# Sheet4.net
KiCad netlist of a schematic drawn in Altium Designer
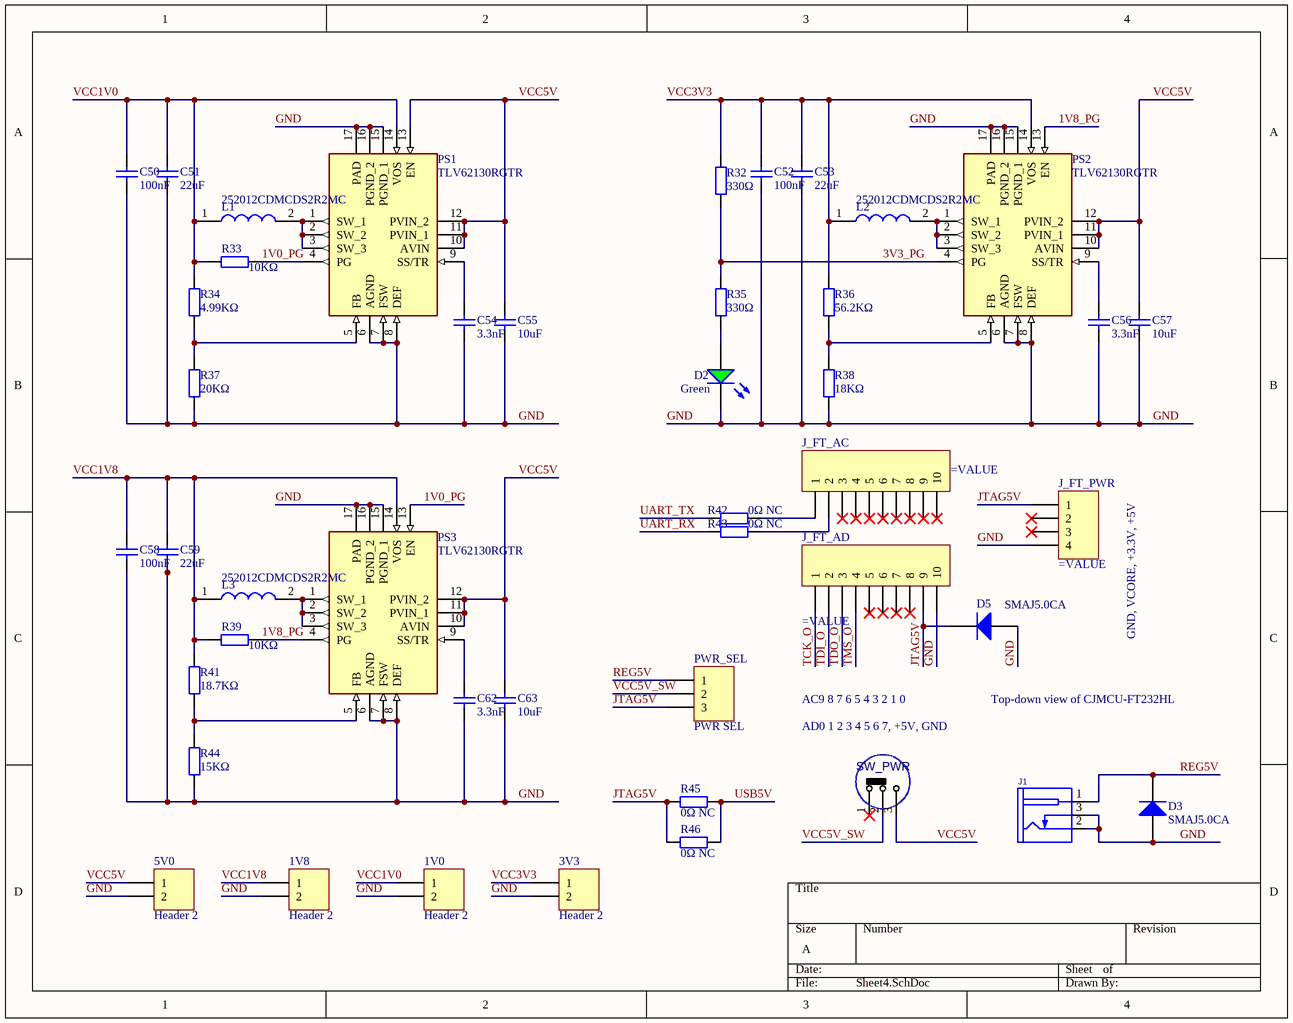
[diagram p0: Sheet4.SchDoc]

(export (version "E")
  (design (tool "Eeschema 10.0.6"))
  (components
    (comp (ref "1V0")
      (value "Header 2")
      (footprint "HDR1X2")
      (description "Header, 2-Pin")
      (fields (field (name "PUBLISHER") "Altium Limited"))
      (libsource (lib "Miscellaneous Connectors") (part "Header 2"))
    )
    (comp (ref "1V8")
      (value "Header 2")
      (footprint "HDR1X2")
      (description "Header, 2-Pin")
      (fields (field (name "PUBLISHER") "Altium Limited"))
      (libsource (lib "Miscellaneous Connectors") (part "Header 2"))
    )
    (comp (ref "3V3")
      (value "Header 2")
      (footprint "HDR1X2")
      (description "Header, 2-Pin")
      (fields (field (name "PUBLISHER") "Altium Limited"))
      (libsource (lib "Miscellaneous Connectors") (part "Header 2"))
    )
    (comp (ref "5V0")
      (value "Header 2")
      (footprint "HDR1X2")
      (description "Header, 2-Pin")
      (fields (field (name "PUBLISHER") "Altium Limited"))
      (libsource (lib "Miscellaneous Connectors") (part "Header 2"))
    )
    (comp (ref "C50")
      (value "100nF")
      (footprint "1206_C")
      (description "贴片电容")
      (libsource (lib "Cap") (part "1206 100nF (104) 10% 50V"))
    )
    (comp (ref "C51")
      (value "22uF")
      (footprint "0805_C")
      (description "贴片电容")
      (libsource (lib "Cap") (part "0805 22uF (226) 20% 25V"))
    )
    (comp (ref "C52")
      (value "100nF")
      (footprint "1206_C")
      (description "贴片电容")
      (libsource (lib "Cap") (part "1206 100nF (104) 10% 50V"))
    )
    (comp (ref "C53")
      (value "22uF")
      (footprint "0805_C")
      (description "贴片电容")
      (libsource (lib "Cap") (part "0805 22uF (226) 20% 25V"))
    )
    (comp (ref "C54")
      (value "3.3nF")
      (footprint "0805_C")
      (description "贴片电容")
      (libsource (lib "Cap") (part "0805 3.3nF (332) 10% 50V"))
    )
    (comp (ref "C55")
      (value "10uF")
      (footprint "1206_C")
      (description "贴片电容")
      (libsource (lib "Cap") (part "1206 10uF (106) 10% 50V"))
    )
    (comp (ref "C56")
      (value "3.3nF")
      (footprint "0805_C")
      (description "贴片电容")
      (libsource (lib "Cap") (part "0805 3.3nF (332) 10% 50V"))
    )
    (comp (ref "C57")
      (value "10uF")
      (footprint "1206_C")
      (description "贴片电容")
      (libsource (lib "Cap") (part "1206 10uF (106) 10% 50V"))
    )
    (comp (ref "C58")
      (value "100nF")
      (footprint "1206_C")
      (description "贴片电容")
      (libsource (lib "Cap") (part "1206 100nF (104) 10% 50V"))
    )
    (comp (ref "C59")
      (value "22uF")
      (footprint "0805_C")
      (description "贴片电容")
      (libsource (lib "Cap") (part "0805 22uF (226) 20% 25V"))
    )
    (comp (ref "C62")
      (value "3.3nF")
      (footprint "0805_C")
      (description "贴片电容")
      (libsource (lib "Cap") (part "0805 3.3nF (332) 10% 50V"))
    )
    (comp (ref "C63")
      (value "10uF")
      (footprint "1206_C")
      (description "贴片电容")
      (libsource (lib "Cap") (part "1206 10uF (106) 10% 50V"))
    )
    (comp (ref "D2")
      (value "Green")
      (footprint "0805_LED_S1")
      (description "发光二极管")
      (libsource (lib "LED") (part "0805 翠绿"))
    )
    (comp (ref "D3")
      (value "SMAJ5.0CA")
      (footprint "SMA(DO-214AC)_S1")
      (description "二极管 TVS")
      (libsource (lib "Diode") (part "SMA(DO-214AC) SS210"))
    )
    (comp (ref "D5")
      (value "SMAJ5.0CA")
      (footprint "SMA(DO-214AC)_S1")
      (description "二极管 TVS")
      (libsource (lib "Diode") (part "SMA(DO-214AC) SS210"))
    )
    (comp (ref "J1")
      (value "DC_POWER_JACK")
      (footprint "JAC_PWR2MM")
      (description "CONN, PWR JACK DC, PLUG DIAM 2.0MM RA THD")
      (fields
        (field (name "MANF") "CUI STACK")
        (field (name "MANF_P#") "PJ-202A, PJ-002AH, PJ-102AH, KLDX-0202")
      )
      (libsource (lib "Connector Power") (part "CONN_PWR_JACK2MM"))
    )
    (comp (ref "J_FT_AC")
      (value "~")
      (footprint "HDR1X10")
      (description "Header, 10-Pin")
      (fields (field (name "PUBLISHER") "Altium Limited"))
      (libsource (lib "Miscellaneous Connectors") (part "Header 10"))
    )
    (comp (ref "J_FT_AD")
      (value "~")
      (footprint "HDR1X10")
      (description "Header, 10-Pin")
      (fields (field (name "PUBLISHER") "Altium Limited"))
      (libsource (lib "Miscellaneous Connectors") (part "Header 10"))
    )
    (comp (ref "J_FT_PWR")
      (value "~")
      (footprint "HDR1X4")
      (description "Header, 4-Pin")
      (fields (field (name "PUBLISHER") "Altium Limited"))
      (libsource (lib "Miscellaneous Connectors") (part "Header 4"))
    )
    (comp (ref "L1")
      (value "252012CDMCDS2R2MC")
      (footprint "SamacSys:INDPM2520X120N")
      (description "Inductor")
      (fields (field (name "MANUFACTURER_PART_NUMBER") "252012CDMCDS‐2R2MC"))
      (libsource (lib "*") (part "252012CDMCDS2R2MC"))
    )
    (comp (ref "L2")
      (value "252012CDMCDS2R2MC")
      (footprint "SamacSys:INDPM2520X120N")
      (description "Inductor")
      (fields (field (name "MANUFACTURER_PART_NUMBER") "252012CDMCDS‐2R2MC"))
      (libsource (lib "*") (part "252012CDMCDS2R2MC"))
    )
    (comp (ref "L3")
      (value "252012CDMCDS2R2MC")
      (footprint "SamacSys:INDPM2520X120N")
      (description "Inductor")
      (fields (field (name "MANUFACTURER_PART_NUMBER") "252012CDMCDS‐2R2MC"))
      (libsource (lib "*") (part "252012CDMCDS2R2MC"))
    )
    (comp (ref "PS1")
      (value "TLV62130RGTR")
      (footprint "SamacSys:QFN50P300X300X100-17N-D")
      (description "Power Supply")
      (fields (field (name "MOUSER PART NUMBER") "595-TLV62130RGTR"))
      (libsource (lib "*") (part "TLV62130RGTR"))
    )
    (comp (ref "PS2")
      (value "TLV62130RGTR")
      (footprint "SamacSys:QFN50P300X300X100-17N-D")
      (description "Power Supply")
      (fields (field (name "MOUSER PART NUMBER") "595-TLV62130RGTR"))
      (libsource (lib "*") (part "TLV62130RGTR"))
    )
    (comp (ref "PS3")
      (value "TLV62130RGTR")
      (footprint "SamacSys:QFN50P300X300X100-17N-D")
      (description "Power Supply")
      (fields (field (name "MOUSER PART NUMBER") "595-TLV62130RGTR"))
      (libsource (lib "*") (part "TLV62130RGTR"))
    )
    (comp (ref "PWR_SEL")
      (value "PWR SEL")
      (footprint "HDR1X3")
      (description "Header, 3-Pin")
      (fields (field (name "PUBLISHER") "Altium Limited"))
      (libsource (lib "Miscellaneous Connectors") (part "Header 3"))
    )
    (comp (ref "R32")
      (value "330Ω")
      (footprint "0805_R")
      (description "贴片电阻")
      (libsource (lib "RES") (part "0805 330Ω (3300) 1%"))
    )
    (comp (ref "R33")
      (value "10KΩ")
      (footprint "1206_R")
      (description "贴片电阻")
      (libsource (lib "RES") (part "1206 10KΩ (1002) 1%"))
    )
    (comp (ref "R34")
      (value "4.99KΩ")
      (footprint "0805_R")
      (description "贴片电阻")
      (libsource (lib "RES") (part "0805 4.99KΩ (4991) 1%"))
    )
    (comp (ref "R35")
      (value "330Ω")
      (footprint "0805_R")
      (description "贴片电阻")
      (libsource (lib "RES") (part "0805 330Ω (3300) 1%"))
    )
    (comp (ref "R36")
      (value "56.2KΩ")
      (footprint "0805_R")
      (description "贴片电阻 56.2k")
      (libsource (lib "RES") (part "0805 56KΩ (5602) 1%"))
    )
    (comp (ref "R37")
      (value "20KΩ")
      (footprint "0805_R")
      (description "贴片电阻")
      (libsource (lib "RES") (part "0805 20KΩ (2002) 1%"))
    )
    (comp (ref "R38")
      (value "18KΩ")
      (footprint "0805_R")
      (description "贴片电阻")
      (libsource (lib "RES") (part "0805 18KΩ (1802) 1%"))
    )
    (comp (ref "R39")
      (value "10KΩ")
      (footprint "1206_R")
      (description "贴片电阻")
      (libsource (lib "RES") (part "1206 10KΩ (1002) 1%"))
    )
    (comp (ref "R41")
      (value "18.7KΩ")
      (footprint "0805_R")
      (description "贴片电阻 18.7k")
      (libsource (lib "RES") (part "0805 18KΩ (1802) 1%"))
    )
    (comp (ref "R42")
      (value "0Ω NC")
      (footprint "0805_R")
      (description "贴片电阻")
      (libsource (lib "RES") (part "0805 0Ω (0R0) 1%"))
    )
    (comp (ref "R43")
      (value "0Ω NC")
      (footprint "0805_R")
      (description "贴片电阻")
      (libsource (lib "RES") (part "0805 0Ω (0R0) 1%"))
    )
    (comp (ref "R44")
      (value "15KΩ")
      (footprint "0805_R")
      (description "贴片电阻")
      (libsource (lib "RES") (part "0805 15KΩ (1502) 1%"))
    )
    (comp (ref "R45")
      (value "0Ω NC")
      (footprint "0805_R")
      (description "贴片电阻")
      (libsource (lib "RES") (part "0805 0Ω (0R0) 1%"))
    )
    (comp (ref "R46")
      (value "0Ω NC")
      (footprint "0805_R")
      (description "贴片电阻")
      (libsource (lib "RES") (part "0805 0Ω (0R0) 1%"))
    )
    (comp (ref "SW_PWR")
      (value "SlideSwitch")
      (footprint "SWSLIDT_SPDT_S_8X4")
      (description "SWITCH, SLIDE, SPDT, 8.6X4.3mm, THD")
      (fields (field (name "MANF") "C&K") (field (name "MANF_PART#") "OS102011MS2QN1"))
      (libsource (lib "Switch Slide") (part "SWSLIDT_SPDT_S_8X4"))
    )
  )
  (nets
    (net (code "1") (name "/1V0_PG") (class "Default")
      (node (ref "PS1") (pin "4") (pinfunction "PG_4") (pintype "output"))
      (node (ref "PS3") (pin "13") (pinfunction "EN_13") (pintype "input"))
      (node (ref "R33") (pin "2") (pinfunction "2_2") (pintype "passive"))
    )
    (net (code "2") (name "/1V8_PG") (class "Default")
      (node (ref "PS2") (pin "13") (pinfunction "EN_13") (pintype "input"))
      (node (ref "PS3") (pin "4") (pinfunction "PG_4") (pintype "output"))
      (node (ref "R39") (pin "2") (pinfunction "2_2") (pintype "passive"))
    )
    (net (code "3") (name "/3V3_PG") (class "Default")
      (node (ref "PS2") (pin "4") (pinfunction "PG_4") (pintype "output"))
      (node (ref "R32") (pin "1") (pinfunction "1_1") (pintype "passive"))
      (node (ref "R35") (pin "2") (pinfunction "2_2") (pintype "passive"))
    )
    (net (code "4") (name "/GND") (class "Default")
      (node (ref "1V0") (pin "2") (pinfunction "2_2") (pintype "passive"))
      (node (ref "1V8") (pin "2") (pinfunction "2_2") (pintype "passive"))
      (node (ref "3V3") (pin "2") (pinfunction "2_2") (pintype "passive"))
      (node (ref "5V0") (pin "2") (pinfunction "2_2") (pintype "passive"))
      (node (ref "C50") (pin "1") (pinfunction "1_1") (pintype "passive"))
      (node (ref "C51") (pin "1") (pinfunction "1_1") (pintype "passive"))
      (node (ref "C52") (pin "1") (pinfunction "1_1") (pintype "passive"))
      (node (ref "C53") (pin "1") (pinfunction "1_1") (pintype "passive"))
      (node (ref "C54") (pin "1") (pinfunction "1_1") (pintype "passive"))
      (node (ref "C55") (pin "1") (pinfunction "1_1") (pintype "passive"))
      (node (ref "C56") (pin "1") (pinfunction "1_1") (pintype "passive"))
      (node (ref "C57") (pin "1") (pinfunction "1_1") (pintype "passive"))
      (node (ref "C58") (pin "1") (pinfunction "1_1") (pintype "passive"))
      (node (ref "C59") (pin "1") (pinfunction "1_1") (pintype "passive"))
      (node (ref "C62") (pin "1") (pinfunction "1_1") (pintype "passive"))
      (node (ref "C63") (pin "1") (pinfunction "1_1") (pintype "passive"))
      (node (ref "D2") (pin "K") (pinfunction "K_K") (pintype "passive"))
      (node (ref "D3") (pin "1") (pinfunction "A_1") (pintype "passive"))
      (node (ref "D5") (pin "1") (pinfunction "A_1") (pintype "passive"))
      (node (ref "J1") (pin "2") (pinfunction "SLEEVE_2") (pintype "power_in"))
      (node (ref "J1") (pin "3") (pinfunction "INSERTION_DET_3") (pintype "power_in"))
      (node (ref "J_FT_AD") (pin "10") (pinfunction "10_10") (pintype "passive"))
      (node (ref "J_FT_PWR") (pin "4") (pinfunction "4_4") (pintype "passive"))
      (node (ref "PS1") (pin "15") (pinfunction "PGND_1_15") (pintype "power_in"))
      (node (ref "PS1") (pin "16") (pinfunction "PGND_2_16") (pintype "power_in"))
      (node (ref "PS1") (pin "17") (pinfunction "PAD_17") (pintype "power_in"))
      (node (ref "PS1") (pin "6") (pinfunction "AGND_6") (pintype "power_in"))
      (node (ref "PS1") (pin "7") (pinfunction "FSW_7") (pintype "input"))
      (node (ref "PS1") (pin "8") (pinfunction "DEF_8") (pintype "input"))
      (node (ref "PS2") (pin "15") (pinfunction "PGND_1_15") (pintype "power_in"))
      (node (ref "PS2") (pin "16") (pinfunction "PGND_2_16") (pintype "power_in"))
      (node (ref "PS2") (pin "17") (pinfunction "PAD_17") (pintype "power_in"))
      (node (ref "PS2") (pin "6") (pinfunction "AGND_6") (pintype "power_in"))
      (node (ref "PS2") (pin "7") (pinfunction "FSW_7") (pintype "input"))
      (node (ref "PS2") (pin "8") (pinfunction "DEF_8") (pintype "input"))
      (node (ref "PS3") (pin "15") (pinfunction "PGND_1_15") (pintype "power_in"))
      (node (ref "PS3") (pin "16") (pinfunction "PGND_2_16") (pintype "power_in"))
      (node (ref "PS3") (pin "17") (pinfunction "PAD_17") (pintype "power_in"))
      (node (ref "PS3") (pin "6") (pinfunction "AGND_6") (pintype "power_in"))
      (node (ref "PS3") (pin "7") (pinfunction "FSW_7") (pintype "input"))
      (node (ref "PS3") (pin "8") (pinfunction "DEF_8") (pintype "input"))
      (node (ref "R37") (pin "1") (pinfunction "1_1") (pintype "passive"))
      (node (ref "R38") (pin "1") (pinfunction "1_1") (pintype "passive"))
      (node (ref "R44") (pin "1") (pinfunction "1_1") (pintype "passive"))
    )
    (net (code "5") (name "/JTAG5V") (class "Default")
      (node (ref "D5") (pin "2") (pinfunction "K_2") (pintype "passive"))
      (node (ref "J_FT_AD") (pin "9") (pinfunction "9_9") (pintype "passive"))
      (node (ref "J_FT_PWR") (pin "1") (pinfunction "1_1") (pintype "passive"))
      (node (ref "PWR_SEL") (pin "3") (pinfunction "3_3") (pintype "passive"))
      (node (ref "R45") (pin "1") (pinfunction "1_1") (pintype "passive"))
      (node (ref "R46") (pin "1") (pinfunction "1_1") (pintype "passive"))
    )
    (net (code "6") (name "/REG5V") (class "Default")
      (node (ref "D3") (pin "2") (pinfunction "K_2") (pintype "passive"))
      (node (ref "J1") (pin "1") (pinfunction "TIP_1") (pintype "power_in"))
      (node (ref "PWR_SEL") (pin "1") (pinfunction "1_1") (pintype "passive"))
    )
    (net (code "7") (name "/TCK_O") (class "Default")
      (node (ref "J_FT_AD") (pin "1") (pinfunction "1_1") (pintype "passive"))
    )
    (net (code "8") (name "/TDI_O") (class "Default")
      (node (ref "J_FT_AD") (pin "2") (pinfunction "2_2") (pintype "passive"))
    )
    (net (code "9") (name "/TDO_O") (class "Default")
      (node (ref "J_FT_AD") (pin "3") (pinfunction "3_3") (pintype "passive"))
    )
    (net (code "10") (name "/TMS_O") (class "Default")
      (node (ref "J_FT_AD") (pin "4") (pinfunction "4_4") (pintype "passive"))
    )
    (net (code "11") (name "/UART_RX") (class "Default")
      (node (ref "R43") (pin "1") (pinfunction "1_1") (pintype "passive"))
    )
    (net (code "12") (name "/UART_TX") (class "Default")
      (node (ref "R42") (pin "1") (pinfunction "1_1") (pintype "passive"))
    )
    (net (code "13") (name "/USB5V") (class "Default")
      (node (ref "R45") (pin "2") (pinfunction "2_2") (pintype "passive"))
      (node (ref "R46") (pin "2") (pinfunction "2_2") (pintype "passive"))
    )
    (net (code "14") (name "/VCC1V0") (class "Default")
      (node (ref "1V0") (pin "1") (pinfunction "1_1") (pintype "passive"))
      (node (ref "C50") (pin "2") (pinfunction "2_2") (pintype "passive"))
      (node (ref "C51") (pin "2") (pinfunction "2_2") (pintype "passive"))
      (node (ref "L1") (pin "1") (pinfunction "1_1") (pintype "passive"))
      (node (ref "PS1") (pin "14") (pinfunction "VOS_14") (pintype "input"))
      (node (ref "R33") (pin "1") (pinfunction "1_1") (pintype "passive"))
      (node (ref "R34") (pin "2") (pinfunction "2_2") (pintype "passive"))
    )
    (net (code "15") (name "/VCC1V8") (class "Default")
      (node (ref "1V8") (pin "1") (pinfunction "1_1") (pintype "passive"))
      (node (ref "C58") (pin "2") (pinfunction "2_2") (pintype "passive"))
      (node (ref "C59") (pin "2") (pinfunction "2_2") (pintype "passive"))
      (node (ref "L3") (pin "1") (pinfunction "1_1") (pintype "passive"))
      (node (ref "PS3") (pin "14") (pinfunction "VOS_14") (pintype "input"))
      (node (ref "R39") (pin "1") (pinfunction "1_1") (pintype "passive"))
      (node (ref "R41") (pin "2") (pinfunction "2_2") (pintype "passive"))
    )
    (net (code "16") (name "/VCC3V3") (class "Default")
      (node (ref "3V3") (pin "1") (pinfunction "1_1") (pintype "passive"))
      (node (ref "C52") (pin "2") (pinfunction "2_2") (pintype "passive"))
      (node (ref "C53") (pin "2") (pinfunction "2_2") (pintype "passive"))
      (node (ref "L2") (pin "1") (pinfunction "1_1") (pintype "passive"))
      (node (ref "PS2") (pin "14") (pinfunction "VOS_14") (pintype "input"))
      (node (ref "R32") (pin "2") (pinfunction "2_2") (pintype "passive"))
      (node (ref "R36") (pin "2") (pinfunction "2_2") (pintype "passive"))
    )
    (net (code "17") (name "/VCC5V") (class "Default")
      (node (ref "5V0") (pin "1") (pinfunction "1_1") (pintype "passive"))
      (node (ref "C55") (pin "2") (pinfunction "2_2") (pintype "passive"))
      (node (ref "C57") (pin "2") (pinfunction "2_2") (pintype "passive"))
      (node (ref "C63") (pin "2") (pinfunction "2_2") (pintype "passive"))
      (node (ref "PS1") (pin "10") (pinfunction "AVIN_10") (pintype "power_in"))
      (node (ref "PS1") (pin "11") (pinfunction "PVIN_1_11") (pintype "power_in"))
      (node (ref "PS1") (pin "12") (pinfunction "PVIN_2_12") (pintype "power_in"))
      (node (ref "PS1") (pin "13") (pinfunction "EN_13") (pintype "input"))
      (node (ref "PS2") (pin "10") (pinfunction "AVIN_10") (pintype "power_in"))
      (node (ref "PS2") (pin "11") (pinfunction "PVIN_1_11") (pintype "power_in"))
      (node (ref "PS2") (pin "12") (pinfunction "PVIN_2_12") (pintype "power_in"))
      (node (ref "PS3") (pin "10") (pinfunction "AVIN_10") (pintype "power_in"))
      (node (ref "PS3") (pin "11") (pinfunction "PVIN_1_11") (pintype "power_in"))
      (node (ref "PS3") (pin "12") (pinfunction "PVIN_2_12") (pintype "power_in"))
      (node (ref "SW_PWR") (pin "3") (pinfunction "P4_3") (pintype "passive"))
    )
    (net (code "18") (name "/VCC5V_SW") (class "Default")
      (node (ref "PWR_SEL") (pin "2") (pinfunction "2_2") (pintype "passive"))
      (node (ref "SW_PWR") (pin "2") (pinfunction "P3_2") (pintype "passive"))
    )
    (net (code "19") (name "Net-(D2-PadA)") (class "Default")
      (node (ref "D2") (pin "A") (pinfunction "A_A") (pintype "passive"))
      (node (ref "R35") (pin "1") (pinfunction "1_1") (pintype "passive"))
    )
    (net (code "20") (name "Net-(J_FT_AC-Pad1)") (class "Default")
      (node (ref "J_FT_AC") (pin "1") (pinfunction "1_1") (pintype "passive"))
      (node (ref "R42") (pin "2") (pinfunction "2_2") (pintype "passive"))
    )
    (net (code "21") (name "Net-(J_FT_AC-Pad2)") (class "Default")
      (node (ref "J_FT_AC") (pin "2") (pinfunction "2_2") (pintype "passive"))
      (node (ref "R43") (pin "2") (pinfunction "2_2") (pintype "passive"))
    )
    (net (code "22") (name "Net-(PS1-FB)") (class "Default")
      (node (ref "PS1") (pin "5") (pinfunction "FB_5") (pintype "input"))
      (node (ref "R34") (pin "1") (pinfunction "1_1") (pintype "passive"))
      (node (ref "R37") (pin "2") (pinfunction "2_2") (pintype "passive"))
    )
    (net (code "23") (name "Net-(PS1-SS{slash}TR)") (class "Default")
      (node (ref "C54") (pin "2") (pinfunction "2_2") (pintype "passive"))
      (node (ref "PS1") (pin "9") (pinfunction "SS/TR_9") (pintype "input"))
    )
    (net (code "24") (name "Net-(PS1-SW_1)") (class "Default")
      (node (ref "L1") (pin "2") (pinfunction "2_2") (pintype "passive"))
      (node (ref "PS1") (pin "1") (pinfunction "SW_1_1") (pintype "output"))
      (node (ref "PS1") (pin "2") (pinfunction "SW_2_2") (pintype "output"))
      (node (ref "PS1") (pin "3") (pinfunction "SW_3_3") (pintype "output"))
    )
    (net (code "25") (name "Net-(PS2-FB)") (class "Default")
      (node (ref "PS2") (pin "5") (pinfunction "FB_5") (pintype "input"))
      (node (ref "R36") (pin "1") (pinfunction "1_1") (pintype "passive"))
      (node (ref "R38") (pin "2") (pinfunction "2_2") (pintype "passive"))
    )
    (net (code "26") (name "Net-(PS2-SS{slash}TR)") (class "Default")
      (node (ref "C56") (pin "2") (pinfunction "2_2") (pintype "passive"))
      (node (ref "PS2") (pin "9") (pinfunction "SS/TR_9") (pintype "input"))
    )
    (net (code "27") (name "Net-(PS2-SW_1)") (class "Default")
      (node (ref "L2") (pin "2") (pinfunction "2_2") (pintype "passive"))
      (node (ref "PS2") (pin "1") (pinfunction "SW_1_1") (pintype "output"))
      (node (ref "PS2") (pin "2") (pinfunction "SW_2_2") (pintype "output"))
      (node (ref "PS2") (pin "3") (pinfunction "SW_3_3") (pintype "output"))
    )
    (net (code "28") (name "Net-(PS3-FB)") (class "Default")
      (node (ref "PS3") (pin "5") (pinfunction "FB_5") (pintype "input"))
      (node (ref "R41") (pin "1") (pinfunction "1_1") (pintype "passive"))
      (node (ref "R44") (pin "2") (pinfunction "2_2") (pintype "passive"))
    )
    (net (code "29") (name "Net-(PS3-SS{slash}TR)") (class "Default")
      (node (ref "C62") (pin "2") (pinfunction "2_2") (pintype "passive"))
      (node (ref "PS3") (pin "9") (pinfunction "SS/TR_9") (pintype "input"))
    )
    (net (code "30") (name "Net-(PS3-SW_1)") (class "Default")
      (node (ref "L3") (pin "2") (pinfunction "2_2") (pintype "passive"))
      (node (ref "PS3") (pin "1") (pinfunction "SW_1_1") (pintype "output"))
      (node (ref "PS3") (pin "2") (pinfunction "SW_2_2") (pintype "output"))
      (node (ref "PS3") (pin "3") (pinfunction "SW_3_3") (pintype "output"))
    )
    (net (code "31") (name "unconnected-(J_FT_AC-Pad3)") (class "Default")
      (node (ref "J_FT_AC") (pin "3") (pinfunction "3_3") (pintype "passive+no_connect"))
    )
    (net (code "32") (name "unconnected-(J_FT_AC-Pad4)") (class "Default")
      (node (ref "J_FT_AC") (pin "4") (pinfunction "4_4") (pintype "passive+no_connect"))
    )
    (net (code "33") (name "unconnected-(J_FT_AC-Pad5)") (class "Default")
      (node (ref "J_FT_AC") (pin "5") (pinfunction "5_5") (pintype "passive+no_connect"))
    )
    (net (code "34") (name "unconnected-(J_FT_AC-Pad6)") (class "Default")
      (node (ref "J_FT_AC") (pin "6") (pinfunction "6_6") (pintype "passive+no_connect"))
    )
    (net (code "35") (name "unconnected-(J_FT_AC-Pad7)") (class "Default")
      (node (ref "J_FT_AC") (pin "7") (pinfunction "7_7") (pintype "passive+no_connect"))
    )
    (net (code "36") (name "unconnected-(J_FT_AC-Pad8)") (class "Default")
      (node (ref "J_FT_AC") (pin "8") (pinfunction "8_8") (pintype "passive+no_connect"))
    )
    (net (code "37") (name "unconnected-(J_FT_AC-Pad9)") (class "Default")
      (node (ref "J_FT_AC") (pin "9") (pinfunction "9_9") (pintype "passive+no_connect"))
    )
    (net (code "38") (name "unconnected-(J_FT_AC-Pad10)") (class "Default")
      (node (ref "J_FT_AC") (pin "10") (pinfunction "10_10") (pintype "passive+no_connect"))
    )
    (net (code "39") (name "unconnected-(J_FT_AD-Pad5)") (class "Default")
      (node (ref "J_FT_AD") (pin "5") (pinfunction "5_5") (pintype "passive+no_connect"))
    )
    (net (code "40") (name "unconnected-(J_FT_AD-Pad6)") (class "Default")
      (node (ref "J_FT_AD") (pin "6") (pinfunction "6_6") (pintype "passive+no_connect"))
    )
    (net (code "41") (name "unconnected-(J_FT_AD-Pad7)") (class "Default")
      (node (ref "J_FT_AD") (pin "7") (pinfunction "7_7") (pintype "passive+no_connect"))
    )
    (net (code "42") (name "unconnected-(J_FT_AD-Pad8)") (class "Default")
      (node (ref "J_FT_AD") (pin "8") (pinfunction "8_8") (pintype "passive+no_connect"))
    )
    (net (code "43") (name "unconnected-(J_FT_PWR-Pad2)") (class "Default")
      (node (ref "J_FT_PWR") (pin "2") (pinfunction "2_2") (pintype "passive+no_connect"))
    )
    (net (code "44") (name "unconnected-(J_FT_PWR-Pad3)") (class "Default")
      (node (ref "J_FT_PWR") (pin "3") (pinfunction "3_3") (pintype "passive+no_connect"))
    )
    (net (code "45") (name "unconnected-(SW_PWR-P1-Pad1)") (class "Default")
      (node (ref "SW_PWR") (pin "1") (pinfunction "P1_1") (pintype "passive+no_connect"))
    )
  )
)
